# Boost_to_1V8.net
KiCad netlist of a schematic drawn in EAGLE
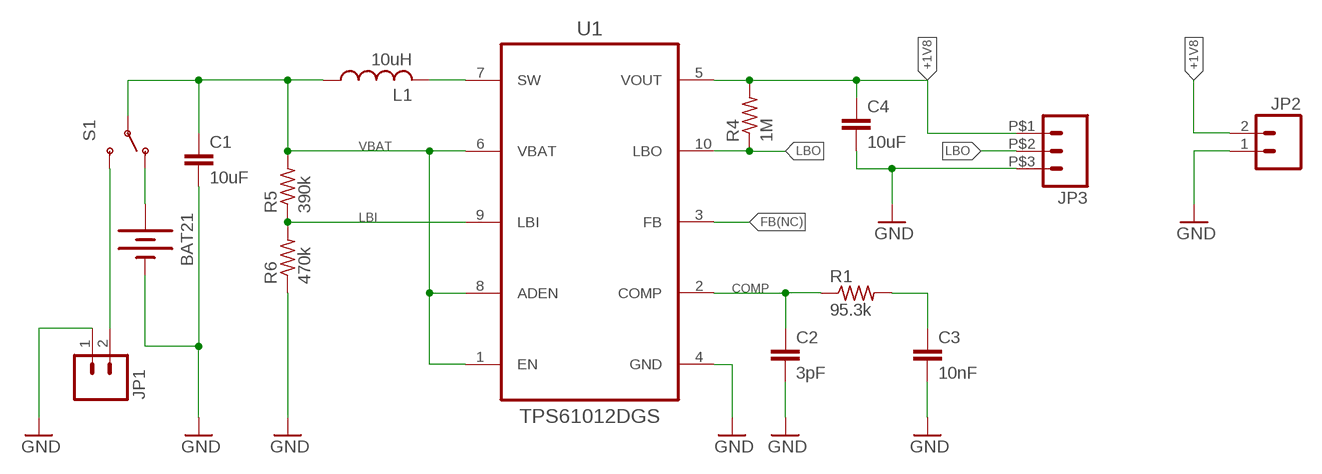
[diagram p0: schematic, sheet 1]

(export (version "E")
  (design (tool "Eeschema 10.0.6"))
  (components
    (comp (ref "BAT21")
      (value "BATTERYAA")
      (footprint "eagle-import:BATTERY-AA")
      (libsource (lib "eagle-import") (part "BATTERYAA"))
    )
    (comp (ref "C1")
      (value "10uF")
      (footprint "eagle-import:C1812")
      (libsource (lib "eagle-import") (part "C-EUC1812"))
    )
    (comp (ref "C2")
      (value "3pF")
      (footprint "eagle-import:C0805")
      (libsource (lib "eagle-import") (part "C-EUC0805"))
    )
    (comp (ref "C3")
      (value "10nF")
      (footprint "eagle-import:C0805")
      (libsource (lib "eagle-import") (part "C-EUC0805"))
    )
    (comp (ref "C4")
      (value "10uF")
      (footprint "eagle-import:C1812")
      (libsource (lib "eagle-import") (part "C-EUC1812"))
    )
    (comp (ref "JP1")
      (value "M02JST-PTH-2")
      (footprint "eagle-import:JST-2-PTH")
      (libsource (lib "eagle-import") (part "M02JST-PTH-2"))
    )
    (comp (ref "JP2")
      (value "M02JST-PTH-2")
      (footprint "eagle-import:JST-2-PTH")
      (libsource (lib "eagle-import") (part "M02JST-PTH-2"))
    )
    (comp (ref "JP3")
      (value "M03")
      (footprint "eagle-import:1X03_282834-3")
      (libsource (lib "eagle-import") (part "M03"))
    )
    (comp (ref "L1")
      (value "10uH")
      (footprint "eagle-import:CDRH6D38")
      (libsource (lib "eagle-import") (part "SUMIDA_POWER_INDUCTOR6"))
    )
    (comp (ref "R1")
      (value "95.3k")
      (footprint "eagle-import:R0805")
      (libsource (lib "eagle-import") (part "R-US_R0805"))
    )
    (comp (ref "R4")
      (value "1M")
      (footprint "eagle-import:R0805")
      (libsource (lib "eagle-import") (part "R-US_R0805"))
    )
    (comp (ref "R5")
      (value "390k")
      (footprint "eagle-import:R0805")
      (libsource (lib "eagle-import") (part "R-US_R0805"))
    )
    (comp (ref "R6")
      (value "470k")
      (footprint "eagle-import:R0805")
      (libsource (lib "eagle-import") (part "R-US_R0805"))
    )
    (comp (ref "S1")
      (value "SWITCH-SPDTPTH")
      (footprint "eagle-import:SWITCH-SPDT")
      (libsource (lib "eagle-import") (part "SWITCH-SPDTPTH"))
    )
    (comp (ref "U1")
      (value "TPS61012DGS")
      (footprint "eagle-import:SOP50P490X110-10N")
      (fields (field (name "VOLTAGE") "1.8"))
      (libsource (lib "eagle-import") (part "TPS6101DGS2"))
    )
  )
  (nets
    (net (code "1") (name "+1V8") (class "Default")
      (node (ref "C4") (pin "1") (pinfunction "1_1") (pintype "passive"))
      (node (ref "JP2") (pin "2") (pinfunction "2_2") (pintype "passive"))
      (node (ref "JP3") (pin "P$1") (pinfunction "1_P$1") (pintype "passive"))
      (node (ref "R4") (pin "2") (pinfunction "2_2") (pintype "passive"))
      (node (ref "U1") (pin "5") (pinfunction "VOUT_5") (pintype "output"))
    )
    (net (code "2") (name "/COMP") (class "Default")
      (node (ref "C2") (pin "1") (pinfunction "1_1") (pintype "passive"))
      (node (ref "R1") (pin "1") (pinfunction "1_1") (pintype "passive"))
      (node (ref "U1") (pin "2") (pinfunction "COMP_2") (pintype "input"))
    )
    (net (code "3") (name "/LBI") (class "Default")
      (node (ref "R5") (pin "1") (pinfunction "1_1") (pintype "passive"))
      (node (ref "R6") (pin "2") (pinfunction "2_2") (pintype "passive"))
      (node (ref "U1") (pin "9") (pinfunction "LBI_9") (pintype "input"))
    )
    (net (code "4") (name "/VBAT") (class "Default")
      (node (ref "C1") (pin "1") (pinfunction "1_1") (pintype "passive"))
      (node (ref "L1") (pin "P$1") (pinfunction "1_P$1") (pintype "passive"))
      (node (ref "R5") (pin "2") (pinfunction "2_2") (pintype "passive"))
      (node (ref "S1") (pin "2") (pinfunction "P_2") (pintype "passive"))
      (node (ref "U1") (pin "1") (pinfunction "EN_1") (pintype "input"))
      (node (ref "U1") (pin "6") (pinfunction "VBAT_6") (pintype "power_in"))
      (node (ref "U1") (pin "8") (pinfunction "ADEN_8") (pintype "input"))
    )
    (net (code "5") (name "FB(NC)") (class "Default")
      (node (ref "U1") (pin "3") (pinfunction "FB_3") (pintype "input"))
    )
    (net (code "6") (name "GND") (class "Default")
      (node (ref "BAT21") (pin "GND@1") (pinfunction "-_GND@1") (pintype "power_in"))
      (node (ref "BAT21") (pin "GND@2") (pinfunction "-_GND@2") (pintype "power_in"))
      (node (ref "C1") (pin "2") (pinfunction "2_2") (pintype "passive"))
      (node (ref "C2") (pin "2") (pinfunction "2_2") (pintype "passive"))
      (node (ref "C3") (pin "2") (pinfunction "2_2") (pintype "passive"))
      (node (ref "C4") (pin "2") (pinfunction "2_2") (pintype "passive"))
      (node (ref "JP1") (pin "1") (pinfunction "1_1") (pintype "passive"))
      (node (ref "JP2") (pin "1") (pinfunction "1_1") (pintype "passive"))
      (node (ref "JP3") (pin "P$3") (pinfunction "3_P$3") (pintype "passive"))
      (node (ref "R6") (pin "1") (pinfunction "1_1") (pintype "passive"))
      (node (ref "U1") (pin "4") (pinfunction "GND_4") (pintype "passive"))
    )
    (net (code "7") (name "LBO") (class "Default")
      (node (ref "JP3") (pin "P$2") (pinfunction "2_P$2") (pintype "passive"))
      (node (ref "R4") (pin "1") (pinfunction "1_1") (pintype "passive"))
      (node (ref "U1") (pin "10") (pinfunction "LBO_10") (pintype "output"))
    )
    (net (code "8") (name "Net-(C3-Pad1)") (class "Default")
      (node (ref "C3") (pin "1") (pinfunction "1_1") (pintype "passive"))
      (node (ref "R1") (pin "2") (pinfunction "2_2") (pintype "passive"))
    )
    (net (code "9") (name "Net-(L1-2)") (class "Default")
      (node (ref "L1") (pin "P$2") (pinfunction "2_P$2") (pintype "passive"))
      (node (ref "U1") (pin "7") (pinfunction "SW_7") (pintype "input"))
    )
    (net (code "10") (name "Net-(S1-O)") (class "Default")
      (node (ref "BAT21") (pin "PWR@1") (pinfunction "+_PWR@1") (pintype "power_in"))
      (node (ref "BAT21") (pin "PWR@2") (pinfunction "+_PWR@2") (pintype "power_in"))
      (node (ref "S1") (pin "1") (pinfunction "O_1") (pintype "passive"))
    )
    (net (code "11") (name "Net-(S1-S)") (class "Default")
      (node (ref "JP1") (pin "2") (pinfunction "2_2") (pintype "passive"))
      (node (ref "S1") (pin "3") (pinfunction "S_3") (pintype "passive"))
    )
  )
)
